# crossroad.net
KiCad netlist of a schematic drawn in EAGLE
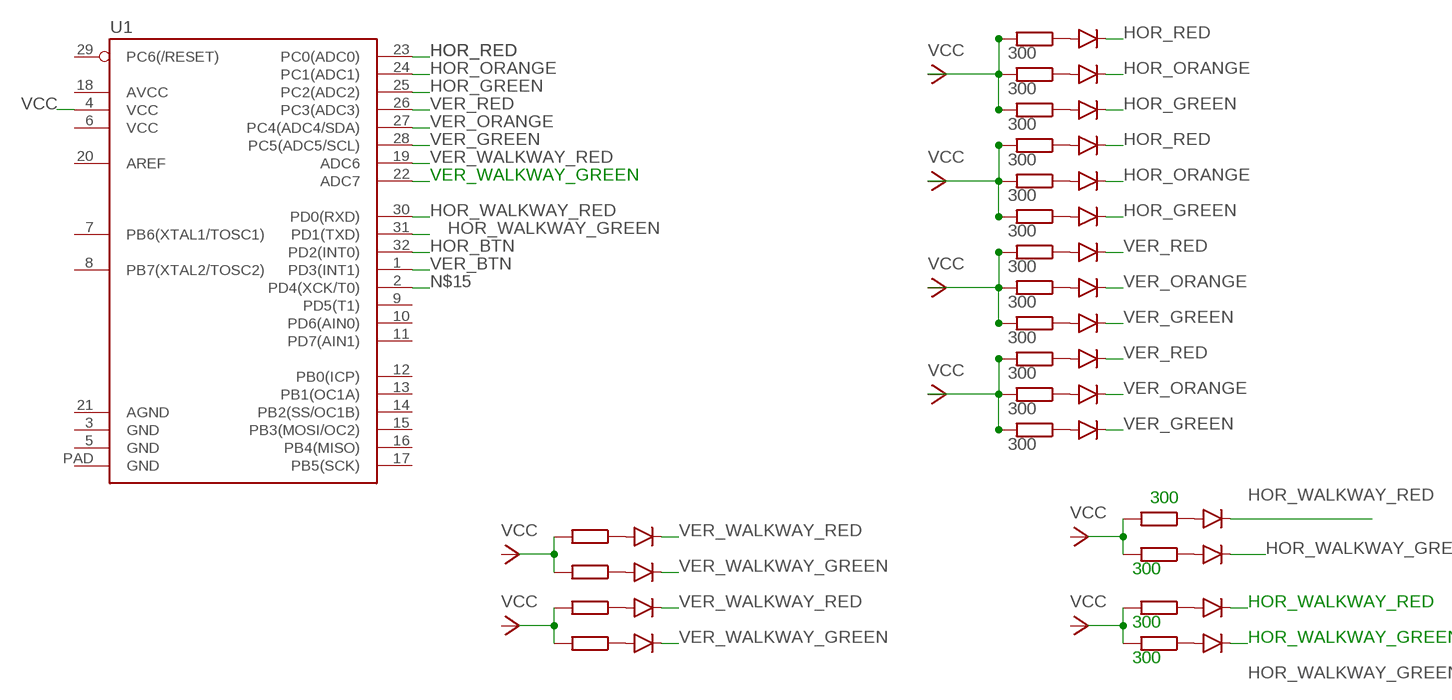
[diagram p0: schematic, sheet 1]

(export (version "E")
  (design (tool "Eeschema 10.0.6"))
  (components
    (comp (ref "D1")
      (value "orange")
      (footprint "eagle-import:DIODE-1N4148")
      (libsource (lib "eagle-import") (part "DIODE1N4148"))
    )
    (comp (ref "D2")
      (value "green")
      (footprint "eagle-import:DIODE-1N4148")
      (libsource (lib "eagle-import") (part "DIODE1N4148"))
    )
    (comp (ref "D3")
      (value "red")
      (footprint "eagle-import:DIODE-1N4148")
      (libsource (lib "eagle-import") (part "DIODE1N4148"))
    )
    (comp (ref "D4")
      (value "orange")
      (footprint "eagle-import:DIODE-1N4148")
      (libsource (lib "eagle-import") (part "DIODE1N4148"))
    )
    (comp (ref "D5")
      (value "green")
      (footprint "eagle-import:DIODE-1N4148")
      (libsource (lib "eagle-import") (part "DIODE1N4148"))
    )
    (comp (ref "D6")
      (value "red")
      (footprint "eagle-import:DIODE-1N4148")
      (libsource (lib "eagle-import") (part "DIODE1N4148"))
    )
    (comp (ref "D7")
      (value "orange")
      (footprint "eagle-import:DIODE-1N4148")
      (libsource (lib "eagle-import") (part "DIODE1N4148"))
    )
    (comp (ref "D8")
      (value "green")
      (footprint "eagle-import:DIODE-1N4148")
      (libsource (lib "eagle-import") (part "DIODE1N4148"))
    )
    (comp (ref "D9")
      (value "red")
      (footprint "eagle-import:DIODE-1N4148")
      (libsource (lib "eagle-import") (part "DIODE1N4148"))
    )
    (comp (ref "D10")
      (value "orange")
      (footprint "eagle-import:DIODE-1N4148")
      (libsource (lib "eagle-import") (part "DIODE1N4148"))
    )
    (comp (ref "D11")
      (value "green")
      (footprint "eagle-import:DIODE-1N4148")
      (libsource (lib "eagle-import") (part "DIODE1N4148"))
    )
    (comp (ref "D12")
      (value "red")
      (footprint "eagle-import:DIODE-1N4148")
      (libsource (lib "eagle-import") (part "DIODE1N4148"))
    )
    (comp (ref "D13")
      (value "red")
      (footprint "eagle-import:DIODE-1N4148")
      (libsource (lib "eagle-import") (part "DIODE1N4148"))
    )
    (comp (ref "D14")
      (value "orange")
      (footprint "eagle-import:DIODE-1N4148")
      (libsource (lib "eagle-import") (part "DIODE1N4148"))
    )
    (comp (ref "D15")
      (value "red")
      (footprint "eagle-import:DIODE-1N4148")
      (libsource (lib "eagle-import") (part "DIODE1N4148"))
    )
    (comp (ref "D16")
      (value "orange")
      (footprint "eagle-import:DIODE-1N4148")
      (libsource (lib "eagle-import") (part "DIODE1N4148"))
    )
    (comp (ref "D17")
      (value "red")
      (footprint "eagle-import:DIODE-1N4148")
      (libsource (lib "eagle-import") (part "DIODE1N4148"))
    )
    (comp (ref "D18")
      (value "orange")
      (footprint "eagle-import:DIODE-1N4148")
      (libsource (lib "eagle-import") (part "DIODE1N4148"))
    )
    (comp (ref "D19")
      (value "red")
      (footprint "eagle-import:DIODE-1N4148")
      (libsource (lib "eagle-import") (part "DIODE1N4148"))
    )
    (comp (ref "D20")
      (value "orange")
      (footprint "eagle-import:DIODE-1N4148")
      (libsource (lib "eagle-import") (part "DIODE1N4148"))
    )
    (comp (ref "R1")
      (value "300")
      (footprint "eagle-import:SMK")
      (libsource (lib "eagle-import") (part "SMK"))
    )
    (comp (ref "R2")
      (value "300")
      (footprint "eagle-import:SMK")
      (libsource (lib "eagle-import") (part "SMK"))
    )
    (comp (ref "R3")
      (value "300")
      (footprint "eagle-import:SMK")
      (libsource (lib "eagle-import") (part "SMK"))
    )
    (comp (ref "R4")
      (value "300")
      (footprint "eagle-import:SMK")
      (libsource (lib "eagle-import") (part "SMK"))
    )
    (comp (ref "R5")
      (value "300")
      (footprint "eagle-import:SMK")
      (libsource (lib "eagle-import") (part "SMK"))
    )
    (comp (ref "R6")
      (value "300")
      (footprint "eagle-import:SMK")
      (libsource (lib "eagle-import") (part "SMK"))
    )
    (comp (ref "R7")
      (value "300")
      (footprint "eagle-import:SMK")
      (libsource (lib "eagle-import") (part "SMK"))
    )
    (comp (ref "R8")
      (value "300")
      (footprint "eagle-import:SMK")
      (libsource (lib "eagle-import") (part "SMK"))
    )
    (comp (ref "R9")
      (value "300")
      (footprint "eagle-import:SMK")
      (libsource (lib "eagle-import") (part "SMK"))
    )
    (comp (ref "R10")
      (value "300")
      (footprint "eagle-import:SMK")
      (libsource (lib "eagle-import") (part "SMK"))
    )
    (comp (ref "R11")
      (value "300")
      (footprint "eagle-import:SMK")
      (libsource (lib "eagle-import") (part "SMK"))
    )
    (comp (ref "R12")
      (value "300")
      (footprint "eagle-import:SMK")
      (libsource (lib "eagle-import") (part "SMK"))
    )
    (comp (ref "R13")
      (value "300")
      (footprint "eagle-import:SMK")
      (libsource (lib "eagle-import") (part "SMK"))
    )
    (comp (ref "R14")
      (value "300")
      (footprint "eagle-import:SMK")
      (libsource (lib "eagle-import") (part "SMK"))
    )
    (comp (ref "R15")
      (value "300")
      (footprint "eagle-import:SMK")
      (libsource (lib "eagle-import") (part "SMK"))
    )
    (comp (ref "R16")
      (value "300")
      (footprint "eagle-import:SMK")
      (libsource (lib "eagle-import") (part "SMK"))
    )
    (comp (ref "R17")
      (value "300")
      (footprint "eagle-import:SMK")
      (libsource (lib "eagle-import") (part "SMK"))
    )
    (comp (ref "R18")
      (value "300")
      (footprint "eagle-import:SMK")
      (libsource (lib "eagle-import") (part "SMK"))
    )
    (comp (ref "R19")
      (value "300")
      (footprint "eagle-import:SMK")
      (libsource (lib "eagle-import") (part "SMK"))
    )
    (comp (ref "R20")
      (value "300")
      (footprint "eagle-import:SMK")
      (libsource (lib "eagle-import") (part "SMK"))
    )
    (comp (ref "U1")
      (value "ATMEGA328P_MLFMLF32")
      (footprint "eagle-import:MLF32-PAD")
      (libsource (lib "eagle-import") (part "ATMEGA328P_MLFMLF32"))
    )
  )
  (nets
    (net (code "1") (name "/HOR_BTN") (class "Default")
      (node (ref "U1") (pin "32") (pinfunction "PD2(INT0)_32") (pintype "bidirectional"))
    )
    (net (code "2") (name "/HOR_GREEN") (class "Default")
      (node (ref "D2") (pin "C") (pinfunction "C_C") (pintype "passive"))
      (node (ref "D5") (pin "C") (pinfunction "C_C") (pintype "passive"))
      (node (ref "U1") (pin "25") (pinfunction "PC2(ADC2)_25") (pintype "bidirectional"))
    )
    (net (code "3") (name "/HOR_ORANGE") (class "Default")
      (node (ref "D1") (pin "C") (pinfunction "C_C") (pintype "passive"))
      (node (ref "D4") (pin "C") (pinfunction "C_C") (pintype "passive"))
      (node (ref "U1") (pin "24") (pinfunction "PC1(ADC1)_24") (pintype "bidirectional"))
    )
    (net (code "4") (name "/HOR_RED") (class "Default")
      (node (ref "D3") (pin "C") (pinfunction "C_C") (pintype "passive"))
      (node (ref "D6") (pin "C") (pinfunction "C_C") (pintype "passive"))
      (node (ref "U1") (pin "23") (pinfunction "PC0(ADC0)_23") (pintype "bidirectional"))
    )
    (net (code "5") (name "/HOR_WALKWAY_GREEN") (class "Default")
      (node (ref "D14") (pin "C") (pinfunction "C_C") (pintype "passive"))
      (node (ref "D16") (pin "C") (pinfunction "C_C") (pintype "passive"))
      (node (ref "U1") (pin "31") (pinfunction "PD1(TXD)_31") (pintype "bidirectional"))
    )
    (net (code "6") (name "/HOR_WALKWAY_RED") (class "Default")
      (node (ref "D13") (pin "C") (pinfunction "C_C") (pintype "passive"))
      (node (ref "D15") (pin "C") (pinfunction "C_C") (pintype "passive"))
      (node (ref "U1") (pin "30") (pinfunction "PD0(RXD)_30") (pintype "bidirectional"))
    )
    (net (code "7") (name "/N$15") (class "Default")
      (node (ref "U1") (pin "2") (pinfunction "PD4(XCK/T0)_2") (pintype "bidirectional"))
    )
    (net (code "8") (name "/VER_BTN") (class "Default")
      (node (ref "U1") (pin "1") (pinfunction "PD3(INT1)_1") (pintype "bidirectional"))
    )
    (net (code "9") (name "/VER_GREEN") (class "Default")
      (node (ref "D11") (pin "C") (pinfunction "C_C") (pintype "passive"))
      (node (ref "D8") (pin "C") (pinfunction "C_C") (pintype "passive"))
      (node (ref "U1") (pin "28") (pinfunction "PC5(ADC5/SCL)_28") (pintype "bidirectional"))
    )
    (net (code "10") (name "/VER_ORANGE") (class "Default")
      (node (ref "D10") (pin "C") (pinfunction "C_C") (pintype "passive"))
      (node (ref "D7") (pin "C") (pinfunction "C_C") (pintype "passive"))
      (node (ref "U1") (pin "27") (pinfunction "PC4(ADC4/SDA)_27") (pintype "bidirectional"))
    )
    (net (code "11") (name "/VER_RED") (class "Default")
      (node (ref "D12") (pin "C") (pinfunction "C_C") (pintype "passive"))
      (node (ref "D9") (pin "C") (pinfunction "C_C") (pintype "passive"))
      (node (ref "U1") (pin "26") (pinfunction "PC3(ADC3)_26") (pintype "bidirectional"))
    )
    (net (code "12") (name "/VER_WALKWAY_GREEN") (class "Default")
      (node (ref "D18") (pin "C") (pinfunction "C_C") (pintype "passive"))
      (node (ref "D20") (pin "C") (pinfunction "C_C") (pintype "passive"))
      (node (ref "U1") (pin "22") (pinfunction "ADC7_22") (pintype "bidirectional"))
    )
    (net (code "13") (name "/VER_WALKWAY_RED") (class "Default")
      (node (ref "D17") (pin "C") (pinfunction "C_C") (pintype "passive"))
      (node (ref "D19") (pin "C") (pinfunction "C_C") (pintype "passive"))
      (node (ref "U1") (pin "19") (pinfunction "ADC6_19") (pintype "bidirectional"))
    )
    (net (code "14") (name "Net-(D1-PadA)") (class "Default")
      (node (ref "D1") (pin "A") (pinfunction "A_A") (pintype "passive"))
      (node (ref "R2") (pin "1") (pinfunction "1_1") (pintype "passive"))
    )
    (net (code "15") (name "Net-(D2-PadA)") (class "Default")
      (node (ref "D2") (pin "A") (pinfunction "A_A") (pintype "passive"))
      (node (ref "R3") (pin "1") (pinfunction "1_1") (pintype "passive"))
    )
    (net (code "16") (name "Net-(D3-PadA)") (class "Default")
      (node (ref "D3") (pin "A") (pinfunction "A_A") (pintype "passive"))
      (node (ref "R1") (pin "1") (pinfunction "1_1") (pintype "passive"))
    )
    (net (code "17") (name "Net-(D4-PadA)") (class "Default")
      (node (ref "D4") (pin "A") (pinfunction "A_A") (pintype "passive"))
      (node (ref "R5") (pin "1") (pinfunction "1_1") (pintype "passive"))
    )
    (net (code "18") (name "Net-(D5-PadA)") (class "Default")
      (node (ref "D5") (pin "A") (pinfunction "A_A") (pintype "passive"))
      (node (ref "R6") (pin "1") (pinfunction "1_1") (pintype "passive"))
    )
    (net (code "19") (name "Net-(D6-PadA)") (class "Default")
      (node (ref "D6") (pin "A") (pinfunction "A_A") (pintype "passive"))
      (node (ref "R4") (pin "1") (pinfunction "1_1") (pintype "passive"))
    )
    (net (code "20") (name "Net-(D7-PadA)") (class "Default")
      (node (ref "D7") (pin "A") (pinfunction "A_A") (pintype "passive"))
      (node (ref "R8") (pin "1") (pinfunction "1_1") (pintype "passive"))
    )
    (net (code "21") (name "Net-(D8-PadA)") (class "Default")
      (node (ref "D8") (pin "A") (pinfunction "A_A") (pintype "passive"))
      (node (ref "R9") (pin "1") (pinfunction "1_1") (pintype "passive"))
    )
    (net (code "22") (name "Net-(D9-PadA)") (class "Default")
      (node (ref "D9") (pin "A") (pinfunction "A_A") (pintype "passive"))
      (node (ref "R7") (pin "1") (pinfunction "1_1") (pintype "passive"))
    )
    (net (code "23") (name "Net-(D10-PadA)") (class "Default")
      (node (ref "D10") (pin "A") (pinfunction "A_A") (pintype "passive"))
      (node (ref "R11") (pin "1") (pinfunction "1_1") (pintype "passive"))
    )
    (net (code "24") (name "Net-(D11-PadA)") (class "Default")
      (node (ref "D11") (pin "A") (pinfunction "A_A") (pintype "passive"))
      (node (ref "R12") (pin "1") (pinfunction "1_1") (pintype "passive"))
    )
    (net (code "25") (name "Net-(D12-PadA)") (class "Default")
      (node (ref "D12") (pin "A") (pinfunction "A_A") (pintype "passive"))
      (node (ref "R10") (pin "1") (pinfunction "1_1") (pintype "passive"))
    )
    (net (code "26") (name "Net-(D13-PadA)") (class "Default")
      (node (ref "D13") (pin "A") (pinfunction "A_A") (pintype "passive"))
      (node (ref "R13") (pin "1") (pinfunction "1_1") (pintype "passive"))
    )
    (net (code "27") (name "Net-(D14-PadA)") (class "Default")
      (node (ref "D14") (pin "A") (pinfunction "A_A") (pintype "passive"))
      (node (ref "R14") (pin "1") (pinfunction "1_1") (pintype "passive"))
    )
    (net (code "28") (name "Net-(D15-PadA)") (class "Default")
      (node (ref "D15") (pin "A") (pinfunction "A_A") (pintype "passive"))
      (node (ref "R15") (pin "1") (pinfunction "1_1") (pintype "passive"))
    )
    (net (code "29") (name "Net-(D16-PadA)") (class "Default")
      (node (ref "D16") (pin "A") (pinfunction "A_A") (pintype "passive"))
      (node (ref "R16") (pin "1") (pinfunction "1_1") (pintype "passive"))
    )
    (net (code "30") (name "Net-(D17-PadA)") (class "Default")
      (node (ref "D17") (pin "A") (pinfunction "A_A") (pintype "passive"))
      (node (ref "R17") (pin "1") (pinfunction "1_1") (pintype "passive"))
    )
    (net (code "31") (name "Net-(D18-PadA)") (class "Default")
      (node (ref "D18") (pin "A") (pinfunction "A_A") (pintype "passive"))
      (node (ref "R18") (pin "1") (pinfunction "1_1") (pintype "passive"))
    )
    (net (code "32") (name "Net-(D19-PadA)") (class "Default")
      (node (ref "D19") (pin "A") (pinfunction "A_A") (pintype "passive"))
      (node (ref "R19") (pin "1") (pinfunction "1_1") (pintype "passive"))
    )
    (net (code "33") (name "Net-(D20-PadA)") (class "Default")
      (node (ref "D20") (pin "A") (pinfunction "A_A") (pintype "passive"))
      (node (ref "R20") (pin "1") (pinfunction "1_1") (pintype "passive"))
    )
    (net (code "34") (name "Net-(R13-Pad2)") (class "Default")
      (node (ref "R13") (pin "2") (pinfunction "2_2") (pintype "passive"))
      (node (ref "R14") (pin "2") (pinfunction "2_2") (pintype "passive"))
    )
    (net (code "35") (name "Net-(R15-Pad2)") (class "Default")
      (node (ref "R15") (pin "2") (pinfunction "2_2") (pintype "passive"))
      (node (ref "R16") (pin "2") (pinfunction "2_2") (pintype "passive"))
    )
    (net (code "36") (name "Net-(R17-Pad2)") (class "Default")
      (node (ref "R17") (pin "2") (pinfunction "2_2") (pintype "passive"))
      (node (ref "R18") (pin "2") (pinfunction "2_2") (pintype "passive"))
    )
    (net (code "37") (name "Net-(R19-Pad2)") (class "Default")
      (node (ref "R19") (pin "2") (pinfunction "2_2") (pintype "passive"))
      (node (ref "R20") (pin "2") (pinfunction "2_2") (pintype "passive"))
    )
    (net (code "38") (name "VCC") (class "Default")
      (node (ref "R1") (pin "2") (pinfunction "2_2") (pintype "passive"))
      (node (ref "R10") (pin "2") (pinfunction "2_2") (pintype "passive"))
      (node (ref "R11") (pin "2") (pinfunction "2_2") (pintype "passive"))
      (node (ref "R12") (pin "2") (pinfunction "2_2") (pintype "passive"))
      (node (ref "R2") (pin "2") (pinfunction "2_2") (pintype "passive"))
      (node (ref "R3") (pin "2") (pinfunction "2_2") (pintype "passive"))
      (node (ref "R4") (pin "2") (pinfunction "2_2") (pintype "passive"))
      (node (ref "R5") (pin "2") (pinfunction "2_2") (pintype "passive"))
      (node (ref "R6") (pin "2") (pinfunction "2_2") (pintype "passive"))
      (node (ref "R7") (pin "2") (pinfunction "2_2") (pintype "passive"))
      (node (ref "R8") (pin "2") (pinfunction "2_2") (pintype "passive"))
      (node (ref "R9") (pin "2") (pinfunction "2_2") (pintype "passive"))
      (node (ref "U1") (pin "4") (pinfunction "VCC_4") (pintype "bidirectional"))
    )
    (net (code "39") (name "unconnected-(U1-AGND-Pad21)") (class "Default")
      (node (ref "U1") (pin "21") (pinfunction "AGND_21") (pintype "bidirectional"))
    )
    (net (code "40") (name "unconnected-(U1-AREF-Pad20)") (class "Default")
      (node (ref "U1") (pin "20") (pinfunction "AREF_20") (pintype "bidirectional"))
    )
    (net (code "41") (name "unconnected-(U1-AVCC-Pad18)") (class "Default")
      (node (ref "U1") (pin "18") (pinfunction "AVCC_18") (pintype "bidirectional"))
    )
    (net (code "42") (name "unconnected-(U1-GND-Pad3)") (class "Default")
      (node (ref "U1") (pin "3") (pinfunction "GND_3") (pintype "bidirectional"))
    )
    (net (code "43") (name "unconnected-(U1-GND-Pad5)") (class "Default")
      (node (ref "U1") (pin "5") (pinfunction "GND_5") (pintype "bidirectional"))
    )
    (net (code "44") (name "unconnected-(U1-GND-PadPAD)") (class "Default")
      (node (ref "U1") (pin "PAD") (pinfunction "GND_PAD") (pintype "bidirectional"))
    )
    (net (code "45") (name "unconnected-(U1-PB0(ICP)-Pad12)") (class "Default")
      (node (ref "U1") (pin "12") (pinfunction "PB0(ICP)_12") (pintype "bidirectional"))
    )
    (net (code "46") (name "unconnected-(U1-PB1(OC1A)-Pad13)") (class "Default")
      (node (ref "U1") (pin "13") (pinfunction "PB1(OC1A)_13") (pintype "bidirectional"))
    )
    (net (code "47") (name "unconnected-(U1-PB2(SS{slash}OC1B)-Pad14)") (class "Default")
      (node (ref "U1") (pin "14") (pinfunction "PB2(SS/OC1B)_14") (pintype "bidirectional"))
    )
    (net (code "48") (name "unconnected-(U1-PB3(MOSI{slash}OC2)-Pad15)") (class "Default")
      (node (ref "U1") (pin "15") (pinfunction "PB3(MOSI/OC2)_15") (pintype "bidirectional"))
    )
    (net (code "49") (name "unconnected-(U1-PB4(MISO)-Pad16)") (class "Default")
      (node (ref "U1") (pin "16") (pinfunction "PB4(MISO)_16") (pintype "bidirectional"))
    )
    (net (code "50") (name "unconnected-(U1-PB5(SCK)-Pad17)") (class "Default")
      (node (ref "U1") (pin "17") (pinfunction "PB5(SCK)_17") (pintype "bidirectional"))
    )
    (net (code "51") (name "unconnected-(U1-PB6(XTAL1{slash}TOSC1)-Pad7)") (class "Default")
      (node (ref "U1") (pin "7") (pinfunction "PB6(XTAL1/TOSC1)_7") (pintype "bidirectional"))
    )
    (net (code "52") (name "unconnected-(U1-PB7(XTAL2{slash}TOSC2)-Pad8)") (class "Default")
      (node (ref "U1") (pin "8") (pinfunction "PB7(XTAL2/TOSC2)_8") (pintype "bidirectional"))
    )
    (net (code "53") (name "unconnected-(U1-PC6({slash}RESET)-Pad29)") (class "Default")
      (node (ref "U1") (pin "29") (pinfunction "PC6(/RESET)_29") (pintype "bidirectional"))
    )
    (net (code "54") (name "unconnected-(U1-PD5(T1)-Pad9)") (class "Default")
      (node (ref "U1") (pin "9") (pinfunction "PD5(T1)_9") (pintype "bidirectional"))
    )
    (net (code "55") (name "unconnected-(U1-PD6(AIN0)-Pad10)") (class "Default")
      (node (ref "U1") (pin "10") (pinfunction "PD6(AIN0)_10") (pintype "bidirectional"))
    )
    (net (code "56") (name "unconnected-(U1-PD7(AIN1)-Pad11)") (class "Default")
      (node (ref "U1") (pin "11") (pinfunction "PD7(AIN1)_11") (pintype "bidirectional"))
    )
    (net (code "57") (name "unconnected-(U1-VCC-Pad6)") (class "Default")
      (node (ref "U1") (pin "6") (pinfunction "VCC_6") (pintype "bidirectional"))
    )
  )
)
